# FULLBRIDGE.net
KiCad netlist of a schematic drawn in EAGLE
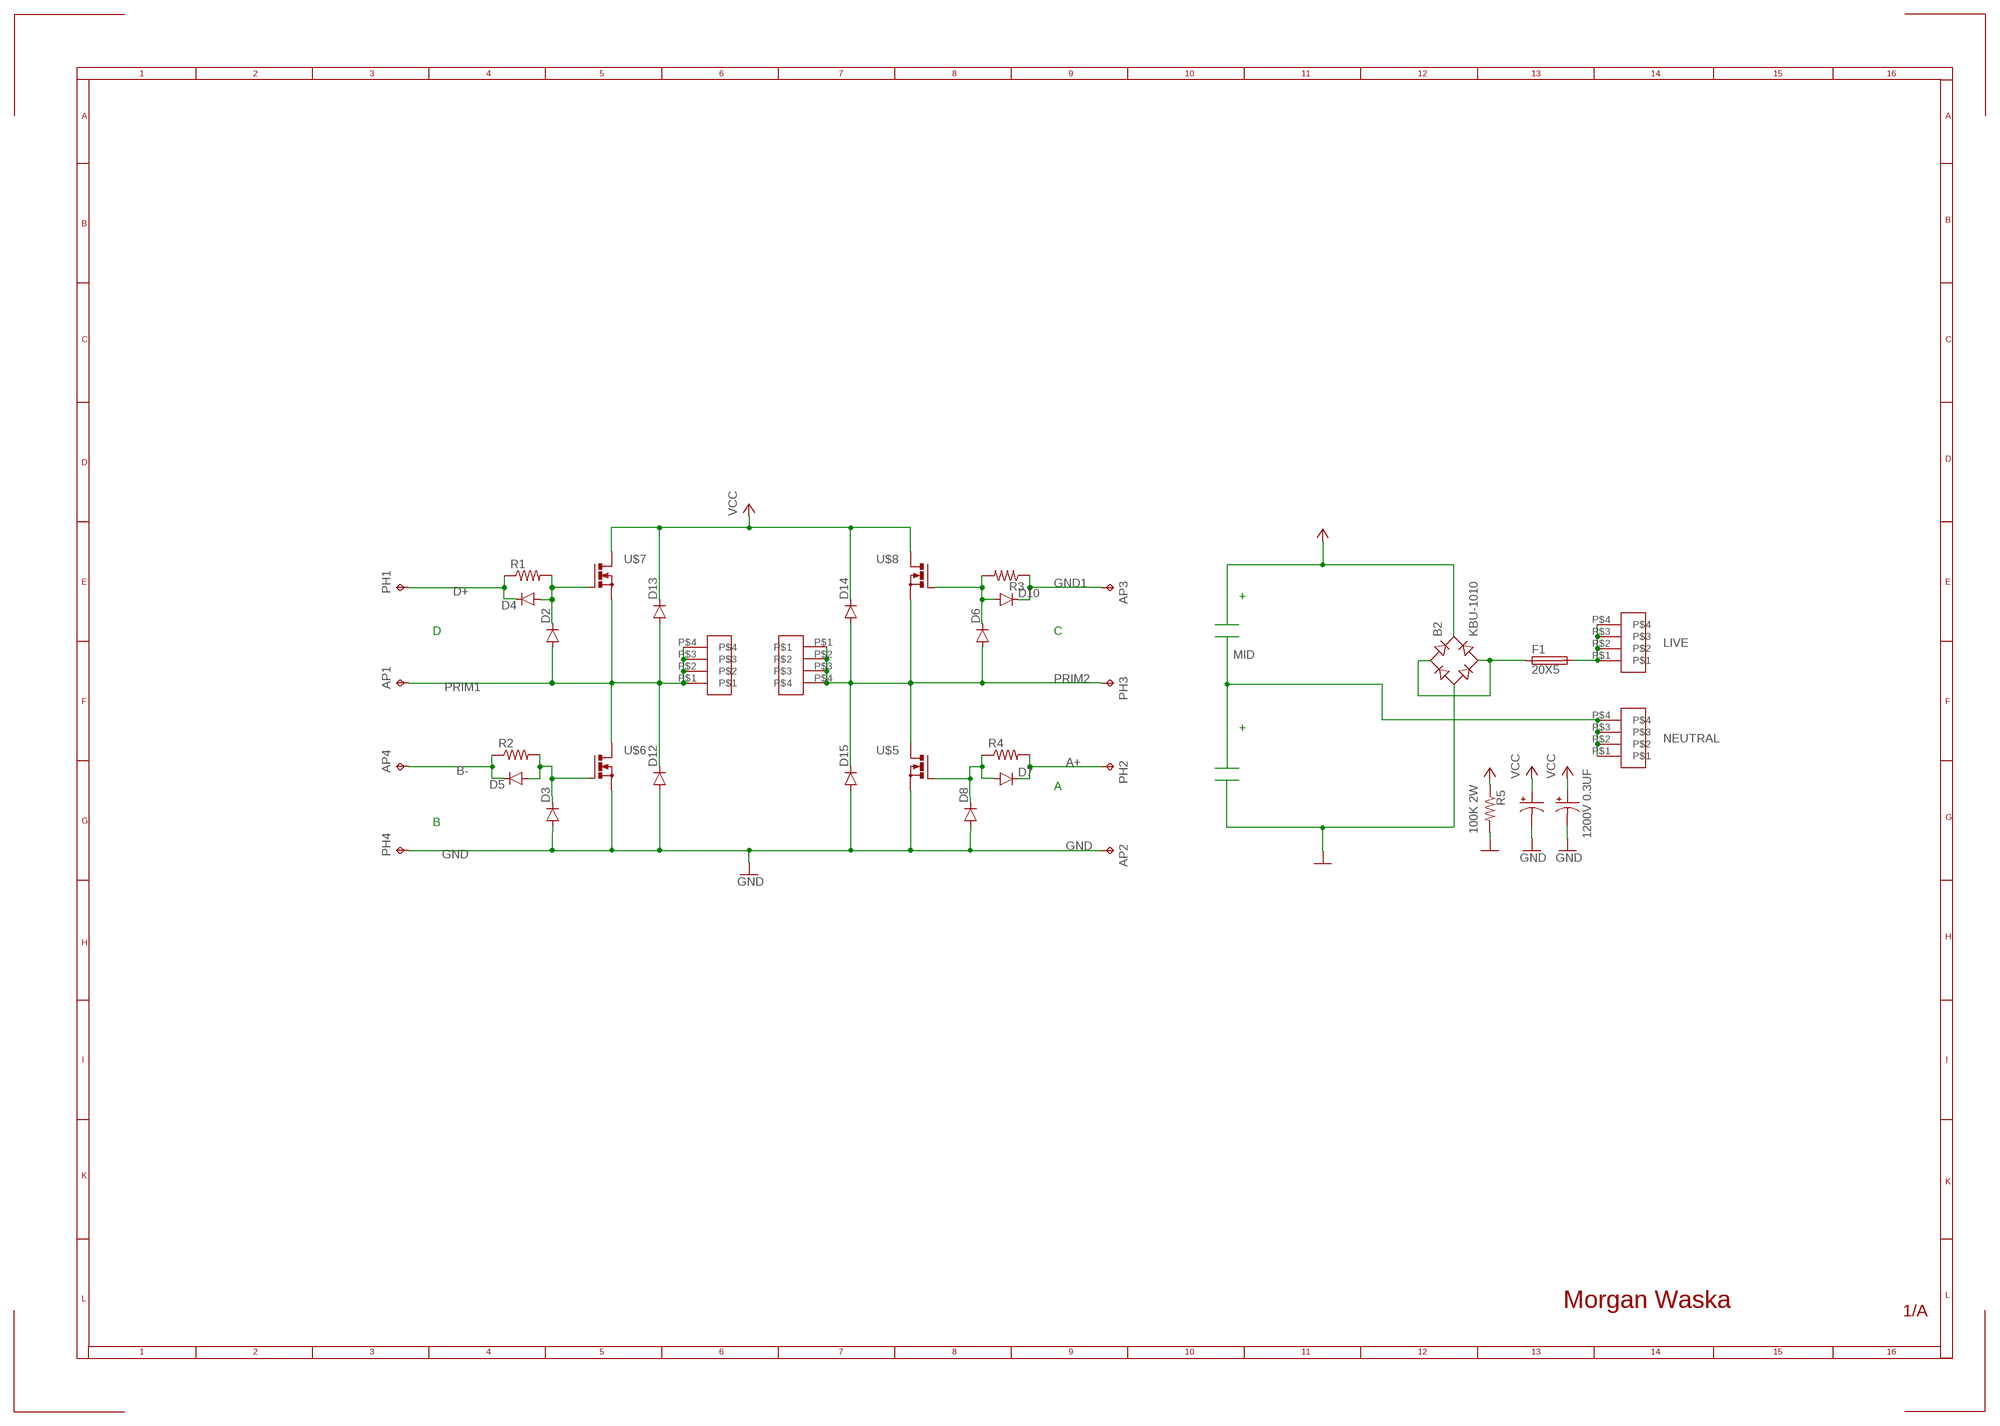
[diagram p0: schematic, sheet 1]

(export (version "E")
  (design (tool "Eeschema 10.0.6"))
  (components
    (comp (ref "AP1")
      (value "TPTP20SQ")
      (footprint "eagle-import:TP20SQ")
      (libsource (lib "eagle-import") (part "TPTP20SQ"))
    )
    (comp (ref "AP2")
      (value "TPTP20SQ")
      (footprint "eagle-import:TP20SQ")
      (libsource (lib "eagle-import") (part "TPTP20SQ"))
    )
    (comp (ref "AP3")
      (value "TPTP20SQ")
      (footprint "eagle-import:TP20SQ")
      (libsource (lib "eagle-import") (part "TPTP20SQ"))
    )
    (comp (ref "AP4")
      (value "TPTP20SQ")
      (footprint "eagle-import:TP20SQ")
      (libsource (lib "eagle-import") (part "TPTP20SQ"))
    )
    (comp (ref "B2")
      (value "KBU-1010")
      (footprint "eagle-import:KBU")
      (libsource (lib "eagle-import") (part "RECTIFIER-KBU"))
    )
    (comp (ref "D2")
      (value "SMAJ26CA")
      (footprint "eagle-import:DO214AC")
      (libsource (lib "eagle-import") (part "DIODE-DO214AC"))
    )
    (comp (ref "D3")
      (value "SMAJ26CA")
      (footprint "eagle-import:DO214AC")
      (libsource (lib "eagle-import") (part "DIODE-DO214AC"))
    )
    (comp (ref "D4")
      (value "SS14-E3/5AT")
      (footprint "eagle-import:DO214AC")
      (libsource (lib "eagle-import") (part "DIODE-DO214AC"))
    )
    (comp (ref "D5")
      (value "SS14-E3/5AT")
      (footprint "eagle-import:DO214AC")
      (libsource (lib "eagle-import") (part "DIODE-DO214AC"))
    )
    (comp (ref "D6")
      (value "SMAJ26CA")
      (footprint "eagle-import:DO214AC")
      (libsource (lib "eagle-import") (part "DIODE-DO214AC"))
    )
    (comp (ref "D7")
      (value "SS14-E3/5AT")
      (footprint "eagle-import:DO214AC")
      (libsource (lib "eagle-import") (part "DIODE-DO214AC"))
    )
    (comp (ref "D8")
      (value "SMAJ26CA")
      (footprint "eagle-import:DO214AC")
      (libsource (lib "eagle-import") (part "DIODE-DO214AC"))
    )
    (comp (ref "D10")
      (value "SS14-E3/5AT")
      (footprint "eagle-import:DO214AC")
      (libsource (lib "eagle-import") (part "DIODE-DO214AC"))
    )
    (comp (ref "D12")
      (value "440V TVS")
      (footprint "eagle-import:DO15-12")
      (libsource (lib "eagle-import") (part "1N5060GP"))
    )
    (comp (ref "D13")
      (value "440V TVS")
      (footprint "eagle-import:DO15-12")
      (libsource (lib "eagle-import") (part "1N5060GP"))
    )
    (comp (ref "D14")
      (value "440V TVS")
      (footprint "eagle-import:DO15-12")
      (libsource (lib "eagle-import") (part "1N5060GP"))
    )
    (comp (ref "D15")
      (value "440V TVS")
      (footprint "eagle-import:DO15-12")
      (libsource (lib "eagle-import") (part "1N5060GP"))
    )
    (comp (ref "F1")
      (value "20X5")
      (footprint "eagle-import:GSH15")
      (fields (field (name "MPN") "64900001039"))
      (libsource (lib "eagle-import") (part "GSH15"))
    )
    (comp (ref "LIVE")
      (value "KEY7788")
      (footprint "eagle-import:7788")
      (libsource (lib "eagle-import") (part "KEY7788"))
    )
    (comp (ref "NEUTRAL")
      (value "KEY7788")
      (footprint "eagle-import:7788")
      (libsource (lib "eagle-import") (part "KEY7788"))
    )
    (comp (ref "PH1")
      (value "TPTP20SQ")
      (footprint "eagle-import:TP20SQ")
      (libsource (lib "eagle-import") (part "TPTP20SQ"))
    )
    (comp (ref "PH2")
      (value "TPTP20SQ")
      (footprint "eagle-import:TP20SQ")
      (libsource (lib "eagle-import") (part "TPTP20SQ"))
    )
    (comp (ref "PH3")
      (value "TPTP20SQ")
      (footprint "eagle-import:TP20SQ")
      (libsource (lib "eagle-import") (part "TPTP20SQ"))
    )
    (comp (ref "PH4")
      (value "TPTP20SQ")
      (footprint "eagle-import:TP20SQ")
      (libsource (lib "eagle-import") (part "TPTP20SQ"))
    )
    (comp (ref "R1")
      (value "R-US_M1206")
      (footprint "eagle-import:M1206")
      (libsource (lib "eagle-import") (part "R-US_M1206"))
    )
    (comp (ref "R2")
      (value "R-US_M1206")
      (footprint "eagle-import:M1206")
      (libsource (lib "eagle-import") (part "R-US_M1206"))
    )
    (comp (ref "R3")
      (value "R-US_M1206")
      (footprint "eagle-import:M1206")
      (libsource (lib "eagle-import") (part "R-US_M1206"))
    )
    (comp (ref "R4")
      (value "R-US_M1206")
      (footprint "eagle-import:M1206")
      (libsource (lib "eagle-import") (part "R-US_M1206"))
    )
    (comp (ref "R5")
      (value "100K 2W")
      (footprint "eagle-import:0411_12")
      (libsource (lib "eagle-import") (part "R-US_0411/12"))
    )
    (comp (ref "U$1")
      (value "KEY7788")
      (footprint "eagle-import:7788")
      (libsource (lib "eagle-import") (part "KEY7788"))
    )
    (comp (ref "U$2")
      (value "KEY7788")
      (footprint "eagle-import:7788")
      (libsource (lib "eagle-import") (part "KEY7788"))
    )
    (comp (ref "U$3")
      (value "CHINEMKP")
      (footprint "eagle-import:CHINESEMKP")
      (libsource (lib "eagle-import") (part "CHINEMKP"))
    )
    (comp (ref "U$4")
      (value "CHINEMKP")
      (footprint "eagle-import:CHINESEMKP")
      (libsource (lib "eagle-import") (part "CHINEMKP"))
    )
    (comp (ref "U$5")
      (value "FGA60N65SMD_SMD")
      (footprint "eagle-import:TO247BH")
      (libsource (lib "eagle-import") (part "FGA60N65SMD_SMD"))
    )
    (comp (ref "U$6")
      (value "FGA60N65SMD_SMD")
      (footprint "eagle-import:TO247BH")
      (libsource (lib "eagle-import") (part "FGA60N65SMD_SMD"))
    )
    (comp (ref "U$7")
      (value "FGA60N65SMD_SMD")
      (footprint "eagle-import:TO247BH")
      (libsource (lib "eagle-import") (part "FGA60N65SMD_SMD"))
    )
    (comp (ref "U$8")
      (value "FGA60N65SMD_SMD")
      (footprint "eagle-import:TO247BH")
      (libsource (lib "eagle-import") (part "FGA60N65SMD_SMD"))
    )
  )
  (nets
    (net (code "1") (name "/A+") (class "Default")
      (node (ref "D7") (pin "C") (pinfunction "C_C") (pintype "passive"))
      (node (ref "PH2") (pin "TP") (pinfunction "TP_TP") (pintype "input"))
      (node (ref "R4") (pin "2") (pinfunction "2_2") (pintype "passive"))
    )
    (net (code "2") (name "/B-") (class "Default")
      (node (ref "AP4") (pin "TP") (pinfunction "TP_TP") (pintype "input"))
      (node (ref "D5") (pin "C") (pinfunction "C_C") (pintype "passive"))
      (node (ref "R2") (pin "1") (pinfunction "1_1") (pintype "passive"))
    )
    (net (code "3") (name "/D+") (class "Default")
      (node (ref "D4") (pin "C") (pinfunction "C_C") (pintype "passive"))
      (node (ref "PH1") (pin "TP") (pinfunction "TP_TP") (pintype "input"))
      (node (ref "R1") (pin "1") (pinfunction "1_1") (pintype "passive"))
    )
    (net (code "4") (name "/GND1") (class "Default")
      (node (ref "AP3") (pin "TP") (pinfunction "TP_TP") (pintype "input"))
      (node (ref "D10") (pin "C") (pinfunction "C_C") (pintype "passive"))
      (node (ref "R3") (pin "1") (pinfunction "1_1") (pintype "passive"))
    )
    (net (code "5") (name "/MID") (class "Default")
      (node (ref "NEUTRAL") (pin "P$1") (pinfunction "P$1_P$1") (pintype "bidirectional"))
      (node (ref "NEUTRAL") (pin "P$2") (pinfunction "P$2_P$2") (pintype "bidirectional"))
      (node (ref "NEUTRAL") (pin "P$3") (pinfunction "P$3_P$3") (pintype "bidirectional"))
      (node (ref "NEUTRAL") (pin "P$4") (pinfunction "P$4_P$4") (pintype "bidirectional"))
    )
    (net (code "6") (name "/PRIM1") (class "Default")
      (node (ref "AP1") (pin "TP") (pinfunction "TP_TP") (pintype "input"))
      (node (ref "D12") (pin "C") (pinfunction "C_C") (pintype "passive"))
      (node (ref "D13") (pin "A") (pinfunction "A_A") (pintype "passive"))
      (node (ref "D2") (pin "A") (pinfunction "A_A") (pintype "passive"))
      (node (ref "U$1") (pin "P$1") (pinfunction "P$1_P$1") (pintype "bidirectional"))
      (node (ref "U$1") (pin "P$2") (pinfunction "P$2_P$2") (pintype "bidirectional"))
      (node (ref "U$1") (pin "P$3") (pinfunction "P$3_P$3") (pintype "bidirectional"))
      (node (ref "U$1") (pin "P$4") (pinfunction "P$4_P$4") (pintype "bidirectional"))
      (node (ref "U$6") (pin "D") (pinfunction "D_D") (pintype "passive"))
      (node (ref "U$7") (pin "S") (pinfunction "S_S") (pintype "passive"))
    )
    (net (code "7") (name "/PRIM2") (class "Default")
      (node (ref "D14") (pin "A") (pinfunction "A_A") (pintype "passive"))
      (node (ref "D15") (pin "C") (pinfunction "C_C") (pintype "passive"))
      (node (ref "D6") (pin "A") (pinfunction "A_A") (pintype "passive"))
      (node (ref "PH3") (pin "TP") (pinfunction "TP_TP") (pintype "input"))
      (node (ref "U$2") (pin "P$1") (pinfunction "P$1_P$1") (pintype "bidirectional"))
      (node (ref "U$2") (pin "P$2") (pinfunction "P$2_P$2") (pintype "bidirectional"))
      (node (ref "U$2") (pin "P$3") (pinfunction "P$3_P$3") (pintype "bidirectional"))
      (node (ref "U$2") (pin "P$4") (pinfunction "P$4_P$4") (pintype "bidirectional"))
      (node (ref "U$5") (pin "D") (pinfunction "D_D") (pintype "passive"))
      (node (ref "U$8") (pin "S") (pinfunction "S_S") (pintype "passive"))
    )
    (net (code "8") (name "GND") (class "Default")
      (node (ref "AP2") (pin "TP") (pinfunction "TP_TP") (pintype "input"))
      (node (ref "B2") (pin "-") (pinfunction "-_-") (pintype "passive"))
      (node (ref "D12") (pin "A") (pinfunction "A_A") (pintype "passive"))
      (node (ref "D15") (pin "A") (pinfunction "A_A") (pintype "passive"))
      (node (ref "D3") (pin "A") (pinfunction "A_A") (pintype "passive"))
      (node (ref "D8") (pin "A") (pinfunction "A_A") (pintype "passive"))
      (node (ref "PH4") (pin "TP") (pinfunction "TP_TP") (pintype "input"))
      (node (ref "R5") (pin "2") (pinfunction "2_2") (pintype "passive"))
      (node (ref "U$3") (pin "P$2") (pinfunction "-_P$2") (pintype "passive"))
      (node (ref "U$4") (pin "P$2") (pinfunction "-_P$2") (pintype "passive"))
      (node (ref "U$5") (pin "S") (pinfunction "S_S") (pintype "passive"))
      (node (ref "U$6") (pin "S") (pinfunction "S_S") (pintype "passive"))
    )
    (net (code "9") (name "Net-(B2-PadAC1)") (class "Default")
      (node (ref "B2") (pin "AC1") (pinfunction "AC1_AC1") (pintype "passive"))
      (node (ref "B2") (pin "AC2") (pinfunction "AC2_AC2") (pintype "passive"))
      (node (ref "F1") (pin "1") (pinfunction "1_1") (pintype "passive"))
    )
    (net (code "10") (name "Net-(D2-PadC)") (class "Default")
      (node (ref "D2") (pin "C") (pinfunction "C_C") (pintype "passive"))
      (node (ref "D4") (pin "A") (pinfunction "A_A") (pintype "passive"))
      (node (ref "R1") (pin "2") (pinfunction "2_2") (pintype "passive"))
      (node (ref "U$7") (pin "G") (pinfunction "G_G") (pintype "passive"))
    )
    (net (code "11") (name "Net-(D3-PadC)") (class "Default")
      (node (ref "D3") (pin "C") (pinfunction "C_C") (pintype "passive"))
      (node (ref "D5") (pin "A") (pinfunction "A_A") (pintype "passive"))
      (node (ref "R2") (pin "2") (pinfunction "2_2") (pintype "passive"))
      (node (ref "U$6") (pin "G") (pinfunction "G_G") (pintype "passive"))
    )
    (net (code "12") (name "Net-(D7-PadA)") (class "Default")
      (node (ref "D7") (pin "A") (pinfunction "A_A") (pintype "passive"))
      (node (ref "D8") (pin "C") (pinfunction "C_C") (pintype "passive"))
      (node (ref "R4") (pin "1") (pinfunction "1_1") (pintype "passive"))
      (node (ref "U$5") (pin "G") (pinfunction "G_G") (pintype "passive"))
    )
    (net (code "13") (name "Net-(D10-PadA)") (class "Default")
      (node (ref "D10") (pin "A") (pinfunction "A_A") (pintype "passive"))
      (node (ref "D6") (pin "C") (pinfunction "C_C") (pintype "passive"))
      (node (ref "R3") (pin "2") (pinfunction "2_2") (pintype "passive"))
      (node (ref "U$8") (pin "G") (pinfunction "G_G") (pintype "passive"))
    )
    (net (code "14") (name "Net-(F1-Pad2)") (class "Default")
      (node (ref "F1") (pin "2") (pinfunction "2_2") (pintype "passive"))
      (node (ref "LIVE") (pin "P$1") (pinfunction "P$1_P$1") (pintype "bidirectional"))
      (node (ref "LIVE") (pin "P$2") (pinfunction "P$2_P$2") (pintype "bidirectional"))
      (node (ref "LIVE") (pin "P$3") (pinfunction "P$3_P$3") (pintype "bidirectional"))
      (node (ref "LIVE") (pin "P$4") (pinfunction "P$4_P$4") (pintype "bidirectional"))
    )
    (net (code "15") (name "VCC") (class "Default")
      (node (ref "B2") (pin "+") (pinfunction "+_+") (pintype "passive"))
      (node (ref "D13") (pin "C") (pinfunction "C_C") (pintype "passive"))
      (node (ref "D14") (pin "C") (pinfunction "C_C") (pintype "passive"))
      (node (ref "R5") (pin "1") (pinfunction "1_1") (pintype "passive"))
      (node (ref "U$3") (pin "P$1") (pinfunction "+_P$1") (pintype "passive"))
      (node (ref "U$4") (pin "P$1") (pinfunction "+_P$1") (pintype "passive"))
      (node (ref "U$7") (pin "D") (pinfunction "D_D") (pintype "passive"))
      (node (ref "U$8") (pin "D") (pinfunction "D_D") (pintype "passive"))
    )
  )
)
